# Test_Jig_BMP1.net
KiCad netlist of a schematic drawn in Altium Designer
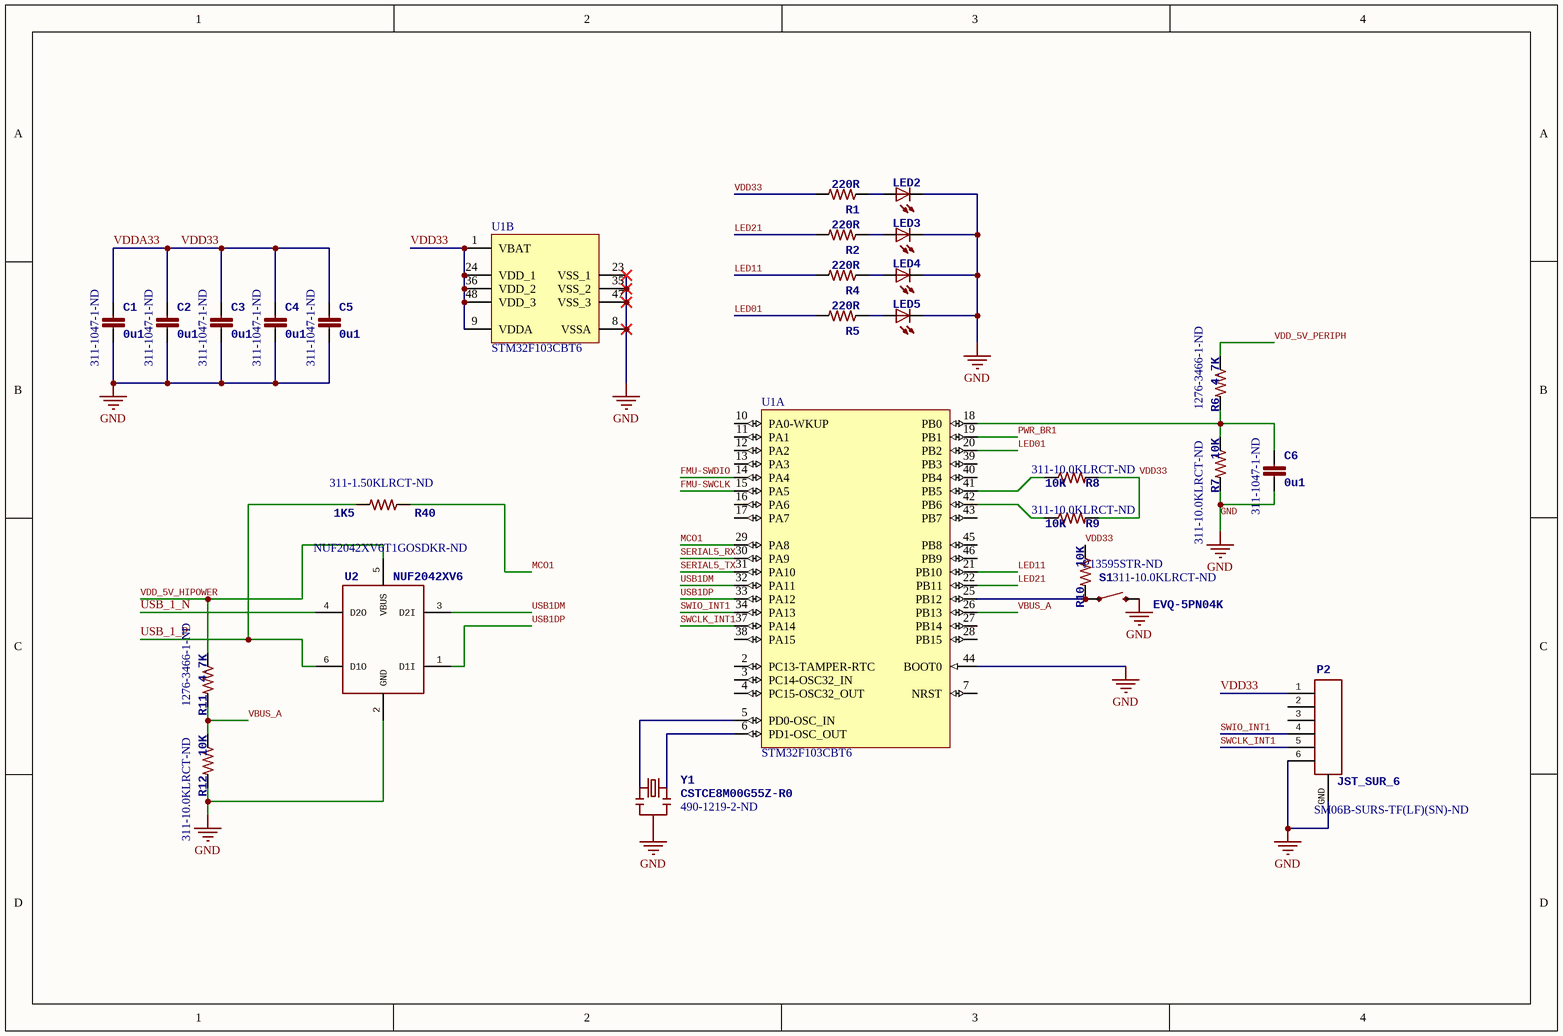
[diagram p0: Test_Jig_BMP1.SchDoc]

(export (version "E")
  (design (tool "Eeschema 10.0.6"))
  (components
    (comp (ref "C1")
      (value "0u1")
      (footprint "0402-CAP")
      (description "CAP CER 0.1UF 16V Y5V 0402")
      (fields
        (field (name "PARTNO") "CC0402ZRY5V7BB104")
        (field (name "SUPPLIER PART NUMBER 1") "311-1047-1-ND")
        (field (name "3DR_PARTNO") "ECM0700")
      )
      (libsource (lib "pixhawk2") (part "CAP0402"))
    )
    (comp (ref "C2")
      (value "0u1")
      (footprint "0402-CAP")
      (description "CAP CER 0.1UF 16V Y5V 0402")
      (fields
        (field (name "PARTNO") "CC0402ZRY5V7BB104")
        (field (name "SUPPLIER PART NUMBER 1") "311-1047-1-ND")
        (field (name "3DR_PARTNO") "ECM0700")
      )
      (libsource (lib "pixhawk2") (part "CAP0402"))
    )
    (comp (ref "C3")
      (value "0u1")
      (footprint "0402-CAP")
      (description "CAP CER 0.1UF 16V Y5V 0402")
      (fields
        (field (name "PARTNO") "CC0402ZRY5V7BB104")
        (field (name "SUPPLIER PART NUMBER 1") "311-1047-1-ND")
        (field (name "3DR_PARTNO") "ECM0700")
      )
      (libsource (lib "pixhawk2") (part "CAP0402"))
    )
    (comp (ref "C4")
      (value "0u1")
      (footprint "0402-CAP")
      (description "CAP CER 0.1UF 16V Y5V 0402")
      (fields
        (field (name "PARTNO") "CC0402ZRY5V7BB104")
        (field (name "SUPPLIER PART NUMBER 1") "311-1047-1-ND")
        (field (name "3DR_PARTNO") "ECM0700")
      )
      (libsource (lib "pixhawk2") (part "CAP0402"))
    )
    (comp (ref "C5")
      (value "0u1")
      (footprint "0402-CAP")
      (description "CAP CER 0.1UF 16V Y5V 0402")
      (fields
        (field (name "PARTNO") "CC0402ZRY5V7BB104")
        (field (name "SUPPLIER PART NUMBER 1") "311-1047-1-ND")
        (field (name "3DR_PARTNO") "ECM0700")
      )
      (libsource (lib "pixhawk2") (part "CAP0402"))
    )
    (comp (ref "C6")
      (value "0u1")
      (footprint "0402-CAP")
      (description "CAP CER 0.1UF 16V Y5V 0402")
      (fields
        (field (name "PARTNO") "CC0402ZRY5V7BB104")
        (field (name "SUPPLIER PART NUMBER 1") "311-1047-1-ND")
        (field (name "3DR_PARTNO") "ECM0700")
      )
      (libsource (lib "pixhawk2") (part "CAP0402"))
    )
    (comp (ref "LED2")
      (value "LED0603_Green")
      (footprint "0603-LED-Blue")
      (description "LED GREEN ROUND CLEAR SMD")
      (fields (field (name "3DR_PARTNO") "ECM0494") (field (name "PARTNO") "APTD1608CGCK"))
      (libsource (lib "pixhawk2") (part "LED0603_Blue"))
    )
    (comp (ref "LED3")
      (value "LED0603_Green")
      (footprint "0603-LED-Blue")
      (description "LED GREEN ROUND CLEAR SMD")
      (fields (field (name "3DR_PARTNO") "ECM0494") (field (name "PARTNO") "APTD1608CGCK"))
      (libsource (lib "pixhawk2") (part "LED0603_Blue"))
    )
    (comp (ref "LED4")
      (value "LED0603_Green")
      (footprint "0603-LED-Blue")
      (description "LED GREEN ROUND CLEAR SMD")
      (fields (field (name "3DR_PARTNO") "ECM0494") (field (name "PARTNO") "APTD1608CGCK"))
      (libsource (lib "pixhawk2") (part "LED0603_Blue"))
    )
    (comp (ref "LED5")
      (value "LED0603_Green")
      (footprint "0603-LED-Blue")
      (description "LED GREEN ROUND CLEAR SMD")
      (fields (field (name "3DR_PARTNO") "ECM0494") (field (name "PARTNO") "APTD1608CGCK"))
      (libsource (lib "pixhawk2") (part "LED0603_Blue"))
    )
    (comp (ref "P2")
      (value "JST_SUR_6")
      (footprint "JST_SUR_H6")
      (description "Connector, Header, 6Pos, .8mm IDC, R/A, SMD, Tin")
      (fields
        (field (name "SUPPLIER PART NUMBER 1") "SM06B-SURS-TF(LF)(SN)-ND")
        (field (name "3DR_PARTNO") "PRT0442")
      )
      (libsource (lib "PCA_0005_FULL_CB_REV_A") (part "JST_SUR_6"))
    )
    (comp (ref "R1")
      (value "220R")
      (footprint "0402-RES")
      (description "RES 220 OHM 1/16W 1% 0402 SMD")
      (fields (field (name "PARTNO") "RC0402FR-07220RL") (field (name "3DR_PARTNO") "ECM0821"))
      (libsource (lib "pixhawk2") (part "RESISTOR0402-RES"))
    )
    (comp (ref "R2")
      (value "220R")
      (footprint "0402-RES")
      (description "RES 220 OHM 1/16W 1% 0402 SMD")
      (fields (field (name "PARTNO") "RC0402FR-07220RL") (field (name "3DR_PARTNO") "ECM0821"))
      (libsource (lib "pixhawk2") (part "RESISTOR0402-RES"))
    )
    (comp (ref "R4")
      (value "220R")
      (footprint "0402-RES")
      (description "RES 220 OHM 1/16W 1% 0402 SMD")
      (fields (field (name "PARTNO") "RC0402FR-07220RL") (field (name "3DR_PARTNO") "ECM0821"))
      (libsource (lib "pixhawk2") (part "RESISTOR0402-RES"))
    )
    (comp (ref "R5")
      (value "220R")
      (footprint "0402-RES")
      (description "RES 220 OHM 1/16W 1% 0402 SMD")
      (fields (field (name "PARTNO") "RC0402FR-07220RL") (field (name "3DR_PARTNO") "ECM0821"))
      (libsource (lib "pixhawk2") (part "RESISTOR0402-RES"))
    )
    (comp (ref "R6")
      (value "4.7K")
      (footprint "0402-RES")
      (description "RES 10K OHM 1/16W 1% 0402 SMD")
      (fields (field (name "PARTNO") "RC1005F472CS") (field (name "SUPPLIER PART NUMBER 1") "1276-3466-1-ND"))
      (libsource (lib "pixhawk2") (part "RESISTOR0402-RES"))
    )
    (comp (ref "R7")
      (value "10K")
      (footprint "0402-RES")
      (description "RES 10K OHM 1/16W 1% 0402 SMD")
      (fields
        (field (name "PARTNO") "RC0402FR-0710KL")
        (field (name "SUPPLIER PART NUMBER 1") "311-10.0KLRCT-ND")
        (field (name "3DR_PARTNO") "ECM0800")
      )
      (libsource (lib "pixhawk2") (part "RESISTOR0402-RES"))
    )
    (comp (ref "R8")
      (value "10K")
      (footprint "0402-RES")
      (description "RES 10K OHM 1/16W 1% 0402 SMD")
      (fields
        (field (name "PARTNO") "RC0402FR-0710KL")
        (field (name "SUPPLIER PART NUMBER 1") "311-10.0KLRCT-ND")
        (field (name "3DR_PARTNO") "ECM0800")
      )
      (libsource (lib "pixhawk2") (part "RESISTOR0402-RES"))
    )
    (comp (ref "R9")
      (value "10K")
      (footprint "0402-RES")
      (description "RES 10K OHM 1/16W 1% 0402 SMD")
      (fields
        (field (name "PARTNO") "RC0402FR-0710KL")
        (field (name "SUPPLIER PART NUMBER 1") "311-10.0KLRCT-ND")
        (field (name "3DR_PARTNO") "ECM0800")
      )
      (libsource (lib "pixhawk2") (part "RESISTOR0402-RES"))
    )
    (comp (ref "R10")
      (value "10K")
      (footprint "0402-RES")
      (description "RES 10K OHM 1/16W 1% 0402 SMD")
      (fields
        (field (name "PARTNO") "RC0402FR-0710KL")
        (field (name "SUPPLIER PART NUMBER 1") "311-10.0KLRCT-ND")
        (field (name "3DR_PARTNO") "ECM0800")
      )
      (libsource (lib "pixhawk2") (part "RESISTOR0402-RES"))
    )
    (comp (ref "R11")
      (value "4.7K")
      (footprint "0402-RES")
      (description "RES 10K OHM 1/16W 1% 0402 SMD")
      (fields (field (name "PARTNO") "RC1005F472CS") (field (name "SUPPLIER PART NUMBER 1") "1276-3466-1-ND"))
      (libsource (lib "pixhawk2") (part "RESISTOR0402-RES"))
    )
    (comp (ref "R12")
      (value "10K")
      (footprint "0402-RES")
      (description "RES 10K OHM 1/16W 1% 0402 SMD")
      (fields
        (field (name "PARTNO") "RC0402FR-0710KL")
        (field (name "SUPPLIER PART NUMBER 1") "311-10.0KLRCT-ND")
        (field (name "3DR_PARTNO") "ECM0800")
      )
      (libsource (lib "pixhawk2") (part "RESISTOR0402-RES"))
    )
    (comp (ref "R40")
      (value "1K5")
      (footprint "0402-RES")
      (description "RES 1.5K OHM 1/16W 1% 0402 SMD")
      (fields
        (field (name "PARTNO") "RC0402FR-071K5L")
        (field (name "SUPPLIER PART NUMBER 1") "311-1.50KLRCT-ND")
        (field (name "3DR_PARTNO") "ECM0803")
      )
      (libsource (lib "pixhawk2") (part "RESISTOR0402-RES"))
    )
    (comp (ref "S1")
      (value "EVQ-5PN04K")
      (footprint "TACTILE-SWITCH-1101NE")
      (fields (field (name "SUPPLIER PART NUMBER 1") "P13595STR-ND"))
      (libsource (lib "pixhawk2") (part "SWITCH-MOMENTARY-2-SMD-1101NE"))
    )
    (comp (ref "U1")
      (value "STM32F103CBT6")
      (footprint "STM-LQFP48_N")
      (libsource (lib "STMicroelectronics STM32 F1") (part "STM32F103CBT6"))
    )
    (comp (ref "U2")
      (value "NUF2042XV6")
      (footprint "SOT563-6")
      (description "IC FILTER USB ESD PROTECT SOT363")
      (fields
        (field (name "PARTNO") "NUF2042XV6T1G")
        (field (name "SUPPLIER PART NUMBER 1") "NUF2042XV6T1GOSDKR-ND")
        (field (name "3DR_PARTNO") "ECM0836")
      )
      (libsource (lib "pixhawk2") (part "NUF2042XV6"))
    )
    (comp (ref "Y1")
      (value "CSTCE8M00G55Z-R0")
      (footprint "RESONATOR-SMD")
      (fields (field (name "SUPPLIER PART NUMBER 1") "490-1219-2-ND"))
      (libsource (lib "SparkFun") (part "RESONATORSMD"))
    )
  )
  (nets
    (net (code "1") (name "/FMU-SWCLK") (class "Default")
      (node (ref "U1") (pin "15") (pinfunction "PA5_15") (pintype "bidirectional"))
    )
    (net (code "2") (name "/FMU-SWDIO") (class "Default")
      (node (ref "U1") (pin "14") (pinfunction "PA4_14") (pintype "bidirectional"))
    )
    (net (code "3") (name "/LED01") (class "Default")
      (node (ref "R5") (pin "P$2") (pinfunction "2_P$2") (pintype "passive"))
      (node (ref "U1") (pin "20") (pinfunction "PB2_20") (pintype "bidirectional"))
    )
    (net (code "4") (name "/LED11") (class "Default")
      (node (ref "R4") (pin "P$2") (pinfunction "2_P$2") (pintype "passive"))
      (node (ref "U1") (pin "21") (pinfunction "PB10_21") (pintype "bidirectional"))
    )
    (net (code "5") (name "/LED21") (class "Default")
      (node (ref "R2") (pin "P$2") (pinfunction "2_P$2") (pintype "passive"))
      (node (ref "U1") (pin "22") (pinfunction "PB11_22") (pintype "bidirectional"))
    )
    (net (code "6") (name "/MCO1") (class "Default")
      (node (ref "R40") (pin "P$1") (pinfunction "1_P$1") (pintype "passive"))
      (node (ref "U1") (pin "29") (pinfunction "PA8_29") (pintype "bidirectional"))
    )
    (net (code "7") (name "/PWR_BR1") (class "Default")
      (node (ref "U1") (pin "19") (pinfunction "PB1_19") (pintype "bidirectional"))
    )
    (net (code "8") (name "/SERIAL5_RX") (class "Default")
      (node (ref "U1") (pin "30") (pinfunction "PA9_30") (pintype "bidirectional"))
    )
    (net (code "9") (name "/SERIAL5_TX") (class "Default")
      (node (ref "U1") (pin "31") (pinfunction "PA10_31") (pintype "bidirectional"))
    )
    (net (code "10") (name "/SWCLK_INT1") (class "Default")
      (node (ref "P2") (pin "5") (pinfunction "5_5") (pintype "passive"))
      (node (ref "U1") (pin "37") (pinfunction "PA14_37") (pintype "bidirectional"))
    )
    (net (code "11") (name "/SWIO_INT1") (class "Default")
      (node (ref "P2") (pin "4") (pinfunction "4_4") (pintype "passive"))
      (node (ref "U1") (pin "34") (pinfunction "PA13_34") (pintype "bidirectional"))
    )
    (net (code "12") (name "/USB1DM") (class "Default")
      (node (ref "U1") (pin "32") (pinfunction "PA11_32") (pintype "bidirectional"))
      (node (ref "U2") (pin "3") (pinfunction "D2I_3") (pintype "passive"))
    )
    (net (code "13") (name "/USB1DP") (class "Default")
      (node (ref "U1") (pin "33") (pinfunction "PA12_33") (pintype "bidirectional"))
      (node (ref "U2") (pin "1") (pinfunction "D1I_1") (pintype "passive"))
    )
    (net (code "14") (name "/USB_1_N") (class "Default")
      (node (ref "U2") (pin "4") (pinfunction "D2O_4") (pintype "passive"))
    )
    (net (code "15") (name "/USB_1_P") (class "Default")
      (node (ref "R40") (pin "P$2") (pinfunction "2_P$2") (pintype "passive"))
      (node (ref "U2") (pin "6") (pinfunction "D1O_6") (pintype "passive"))
    )
    (net (code "16") (name "/VBUS_A") (class "Default")
      (node (ref "R11") (pin "P$2") (pinfunction "2_P$2") (pintype "passive"))
      (node (ref "R12") (pin "P$1") (pinfunction "1_P$1") (pintype "passive"))
      (node (ref "U1") (pin "26") (pinfunction "PB13_26") (pintype "bidirectional"))
    )
    (net (code "17") (name "/VDD33") (class "Default")
      (node (ref "C1") (pin "P$1") (pinfunction "1_P$1") (pintype "passive"))
      (node (ref "C2") (pin "P$1") (pinfunction "1_P$1") (pintype "passive"))
      (node (ref "C3") (pin "P$1") (pinfunction "1_P$1") (pintype "passive"))
      (node (ref "C4") (pin "P$1") (pinfunction "1_P$1") (pintype "passive"))
      (node (ref "C5") (pin "P$1") (pinfunction "1_P$1") (pintype "passive"))
      (node (ref "P2") (pin "1") (pinfunction "1_1") (pintype "passive"))
      (node (ref "R1") (pin "P$2") (pinfunction "2_P$2") (pintype "passive"))
      (node (ref "R10") (pin "P$1") (pinfunction "1_P$1") (pintype "passive"))
      (node (ref "R8") (pin "P$2") (pinfunction "2_P$2") (pintype "passive"))
      (node (ref "R9") (pin "P$2") (pinfunction "2_P$2") (pintype "passive"))
      (node (ref "U1") (pin "1") (pinfunction "VBAT_1") (pintype "power_in"))
      (node (ref "U1") (pin "24") (pinfunction "VDD_1_24") (pintype "power_in"))
      (node (ref "U1") (pin "36") (pinfunction "VDD_2_36") (pintype "power_in"))
      (node (ref "U1") (pin "48") (pinfunction "VDD_3_48") (pintype "power_in"))
      (node (ref "U1") (pin "9") (pinfunction "VDDA_9") (pintype "power_in"))
    )
    (net (code "18") (name "/VDD_5V_HIPOWER") (class "Default")
      (node (ref "R11") (pin "P$1") (pinfunction "1_P$1") (pintype "passive"))
      (node (ref "U2") (pin "5") (pinfunction "VBUS_5") (pintype "passive"))
    )
    (net (code "19") (name "/VDD_5V_PERIPH") (class "Default")
      (node (ref "R6") (pin "P$1") (pinfunction "1_P$1") (pintype "passive"))
    )
    (net (code "20") (name "GND") (class "Default")
      (node (ref "C1") (pin "P$2") (pinfunction "2_P$2") (pintype "passive"))
      (node (ref "C2") (pin "P$2") (pinfunction "2_P$2") (pintype "passive"))
      (node (ref "C3") (pin "P$2") (pinfunction "2_P$2") (pintype "passive"))
      (node (ref "C4") (pin "P$2") (pinfunction "2_P$2") (pintype "passive"))
      (node (ref "C5") (pin "P$2") (pinfunction "2_P$2") (pintype "passive"))
      (node (ref "C6") (pin "P$2") (pinfunction "2_P$2") (pintype "passive"))
      (node (ref "LED2") (pin "C") (pinfunction "C_C") (pintype "passive"))
      (node (ref "LED3") (pin "C") (pinfunction "C_C") (pintype "passive"))
      (node (ref "LED4") (pin "C") (pinfunction "C_C") (pintype "passive"))
      (node (ref "LED5") (pin "C") (pinfunction "C_C") (pintype "passive"))
      (node (ref "P2") (pin "6") (pinfunction "6_6") (pintype "passive"))
      (node (ref "P2") (pin "GND") (pinfunction "GND_GND") (pintype "passive"))
      (node (ref "R12") (pin "P$2") (pinfunction "2_P$2") (pintype "passive"))
      (node (ref "R7") (pin "P$2") (pinfunction "2_P$2") (pintype "passive"))
      (node (ref "S1") (pin "2") (pinfunction "2_2") (pintype "passive"))
      (node (ref "U1") (pin "23") (pinfunction "VSS_1_23") (pintype "power_in"))
      (node (ref "U1") (pin "35") (pinfunction "VSS_2_35") (pintype "power_in"))
      (node (ref "U1") (pin "44") (pinfunction "BOOT0_44") (pintype "input"))
      (node (ref "U1") (pin "47") (pinfunction "VSS_3_47") (pintype "power_in"))
      (node (ref "U1") (pin "8") (pinfunction "VSSA_8") (pintype "power_in"))
      (node (ref "U2") (pin "2") (pinfunction "GND_2") (pintype "passive"))
      (node (ref "Y1") (pin "2") (pinfunction "2_2") (pintype "passive"))
    )
    (net (code "21") (name "Net-(C6-1)") (class "Default")
      (node (ref "C6") (pin "P$1") (pinfunction "1_P$1") (pintype "passive"))
      (node (ref "R6") (pin "P$2") (pinfunction "2_P$2") (pintype "passive"))
      (node (ref "R7") (pin "P$1") (pinfunction "1_P$1") (pintype "passive"))
      (node (ref "U1") (pin "18") (pinfunction "PB0_18") (pintype "bidirectional"))
    )
    (net (code "22") (name "Net-(R1-1)") (class "Default")
      (node (ref "LED2") (pin "A") (pinfunction "A_A") (pintype "passive"))
      (node (ref "R1") (pin "P$1") (pinfunction "1_P$1") (pintype "passive"))
    )
    (net (code "23") (name "Net-(R2-1)") (class "Default")
      (node (ref "LED3") (pin "A") (pinfunction "A_A") (pintype "passive"))
      (node (ref "R2") (pin "P$1") (pinfunction "1_P$1") (pintype "passive"))
    )
    (net (code "24") (name "Net-(R4-1)") (class "Default")
      (node (ref "LED4") (pin "A") (pinfunction "A_A") (pintype "passive"))
      (node (ref "R4") (pin "P$1") (pinfunction "1_P$1") (pintype "passive"))
    )
    (net (code "25") (name "Net-(R5-1)") (class "Default")
      (node (ref "LED5") (pin "A") (pinfunction "A_A") (pintype "passive"))
      (node (ref "R5") (pin "P$1") (pinfunction "1_P$1") (pintype "passive"))
    )
    (net (code "26") (name "Net-(R8-1)") (class "Default")
      (node (ref "R8") (pin "P$1") (pinfunction "1_P$1") (pintype "passive"))
      (node (ref "U1") (pin "41") (pinfunction "PB5_41") (pintype "bidirectional"))
    )
    (net (code "27") (name "Net-(R9-1)") (class "Default")
      (node (ref "R9") (pin "P$1") (pinfunction "1_P$1") (pintype "passive"))
      (node (ref "U1") (pin "42") (pinfunction "PB6_42") (pintype "bidirectional"))
    )
    (net (code "28") (name "Net-(R10-2)") (class "Default")
      (node (ref "R10") (pin "P$2") (pinfunction "2_P$2") (pintype "passive"))
      (node (ref "S1") (pin "1") (pinfunction "1_1") (pintype "passive"))
      (node (ref "U1") (pin "25") (pinfunction "PB12_25") (pintype "bidirectional"))
    )
    (net (code "29") (name "Net-(U1A-PD0-OSC_IN)") (class "Default")
      (node (ref "U1") (pin "5") (pinfunction "PD0-OSC_IN_5") (pintype "bidirectional"))
      (node (ref "Y1") (pin "1") (pinfunction "1_1") (pintype "passive"))
    )
    (net (code "30") (name "Net-(U1A-PD1-OSC_OUT)") (class "Default")
      (node (ref "U1") (pin "6") (pinfunction "PD1-OSC_OUT_6") (pintype "bidirectional"))
      (node (ref "Y1") (pin "3") (pinfunction "3_3") (pintype "passive"))
    )
    (net (code "31") (name "unconnected-(P2-Pad2)") (class "Default")
      (node (ref "P2") (pin "2") (pinfunction "2_2") (pintype "passive"))
    )
    (net (code "32") (name "unconnected-(P2-Pad3)") (class "Default")
      (node (ref "P2") (pin "3") (pinfunction "3_3") (pintype "passive"))
    )
    (net (code "33") (name "unconnected-(U1A-NRST-Pad7)") (class "Default")
      (node (ref "U1") (pin "7") (pinfunction "NRST_7") (pintype "bidirectional"))
    )
    (net (code "34") (name "unconnected-(U1A-PA0-WKUP-Pad10)") (class "Default")
      (node (ref "U1") (pin "10") (pinfunction "PA0-WKUP_10") (pintype "bidirectional"))
    )
    (net (code "35") (name "unconnected-(U1A-PA1-Pad11)") (class "Default")
      (node (ref "U1") (pin "11") (pinfunction "PA1_11") (pintype "bidirectional"))
    )
    (net (code "36") (name "unconnected-(U1A-PA2-Pad12)") (class "Default")
      (node (ref "U1") (pin "12") (pinfunction "PA2_12") (pintype "bidirectional"))
    )
    (net (code "37") (name "unconnected-(U1A-PA3-Pad13)") (class "Default")
      (node (ref "U1") (pin "13") (pinfunction "PA3_13") (pintype "bidirectional"))
    )
    (net (code "38") (name "unconnected-(U1A-PA6-Pad16)") (class "Default")
      (node (ref "U1") (pin "16") (pinfunction "PA6_16") (pintype "bidirectional"))
    )
    (net (code "39") (name "unconnected-(U1A-PA7-Pad17)") (class "Default")
      (node (ref "U1") (pin "17") (pinfunction "PA7_17") (pintype "bidirectional"))
    )
    (net (code "40") (name "unconnected-(U1A-PA15-Pad38)") (class "Default")
      (node (ref "U1") (pin "38") (pinfunction "PA15_38") (pintype "bidirectional"))
    )
    (net (code "41") (name "unconnected-(U1A-PB3-Pad39)") (class "Default")
      (node (ref "U1") (pin "39") (pinfunction "PB3_39") (pintype "bidirectional"))
    )
    (net (code "42") (name "unconnected-(U1A-PB4-Pad40)") (class "Default")
      (node (ref "U1") (pin "40") (pinfunction "PB4_40") (pintype "bidirectional"))
    )
    (net (code "43") (name "unconnected-(U1A-PB7-Pad43)") (class "Default")
      (node (ref "U1") (pin "43") (pinfunction "PB7_43") (pintype "bidirectional"))
    )
    (net (code "44") (name "unconnected-(U1A-PB8-Pad45)") (class "Default")
      (node (ref "U1") (pin "45") (pinfunction "PB8_45") (pintype "bidirectional"))
    )
    (net (code "45") (name "unconnected-(U1A-PB9-Pad46)") (class "Default")
      (node (ref "U1") (pin "46") (pinfunction "PB9_46") (pintype "bidirectional"))
    )
    (net (code "46") (name "unconnected-(U1A-PB14-Pad27)") (class "Default")
      (node (ref "U1") (pin "27") (pinfunction "PB14_27") (pintype "bidirectional"))
    )
    (net (code "47") (name "unconnected-(U1A-PB15-Pad28)") (class "Default")
      (node (ref "U1") (pin "28") (pinfunction "PB15_28") (pintype "bidirectional"))
    )
    (net (code "48") (name "unconnected-(U1A-PC13-TAMPER-RTC-Pad2)") (class "Default")
      (node (ref "U1") (pin "2") (pinfunction "PC13-TAMPER-RTC_2") (pintype "bidirectional"))
    )
    (net (code "49") (name "unconnected-(U1A-PC14-OSC32_IN-Pad3)") (class "Default")
      (node (ref "U1") (pin "3") (pinfunction "PC14-OSC32_IN_3") (pintype "bidirectional"))
    )
    (net (code "50") (name "unconnected-(U1A-PC15-OSC32_OUT-Pad4)") (class "Default")
      (node (ref "U1") (pin "4") (pinfunction "PC15-OSC32_OUT_4") (pintype "bidirectional"))
    )
  )
)
